# RGBMainBoard_-_SCH.net
KiCad netlist of a schematic drawn in Altium Designer
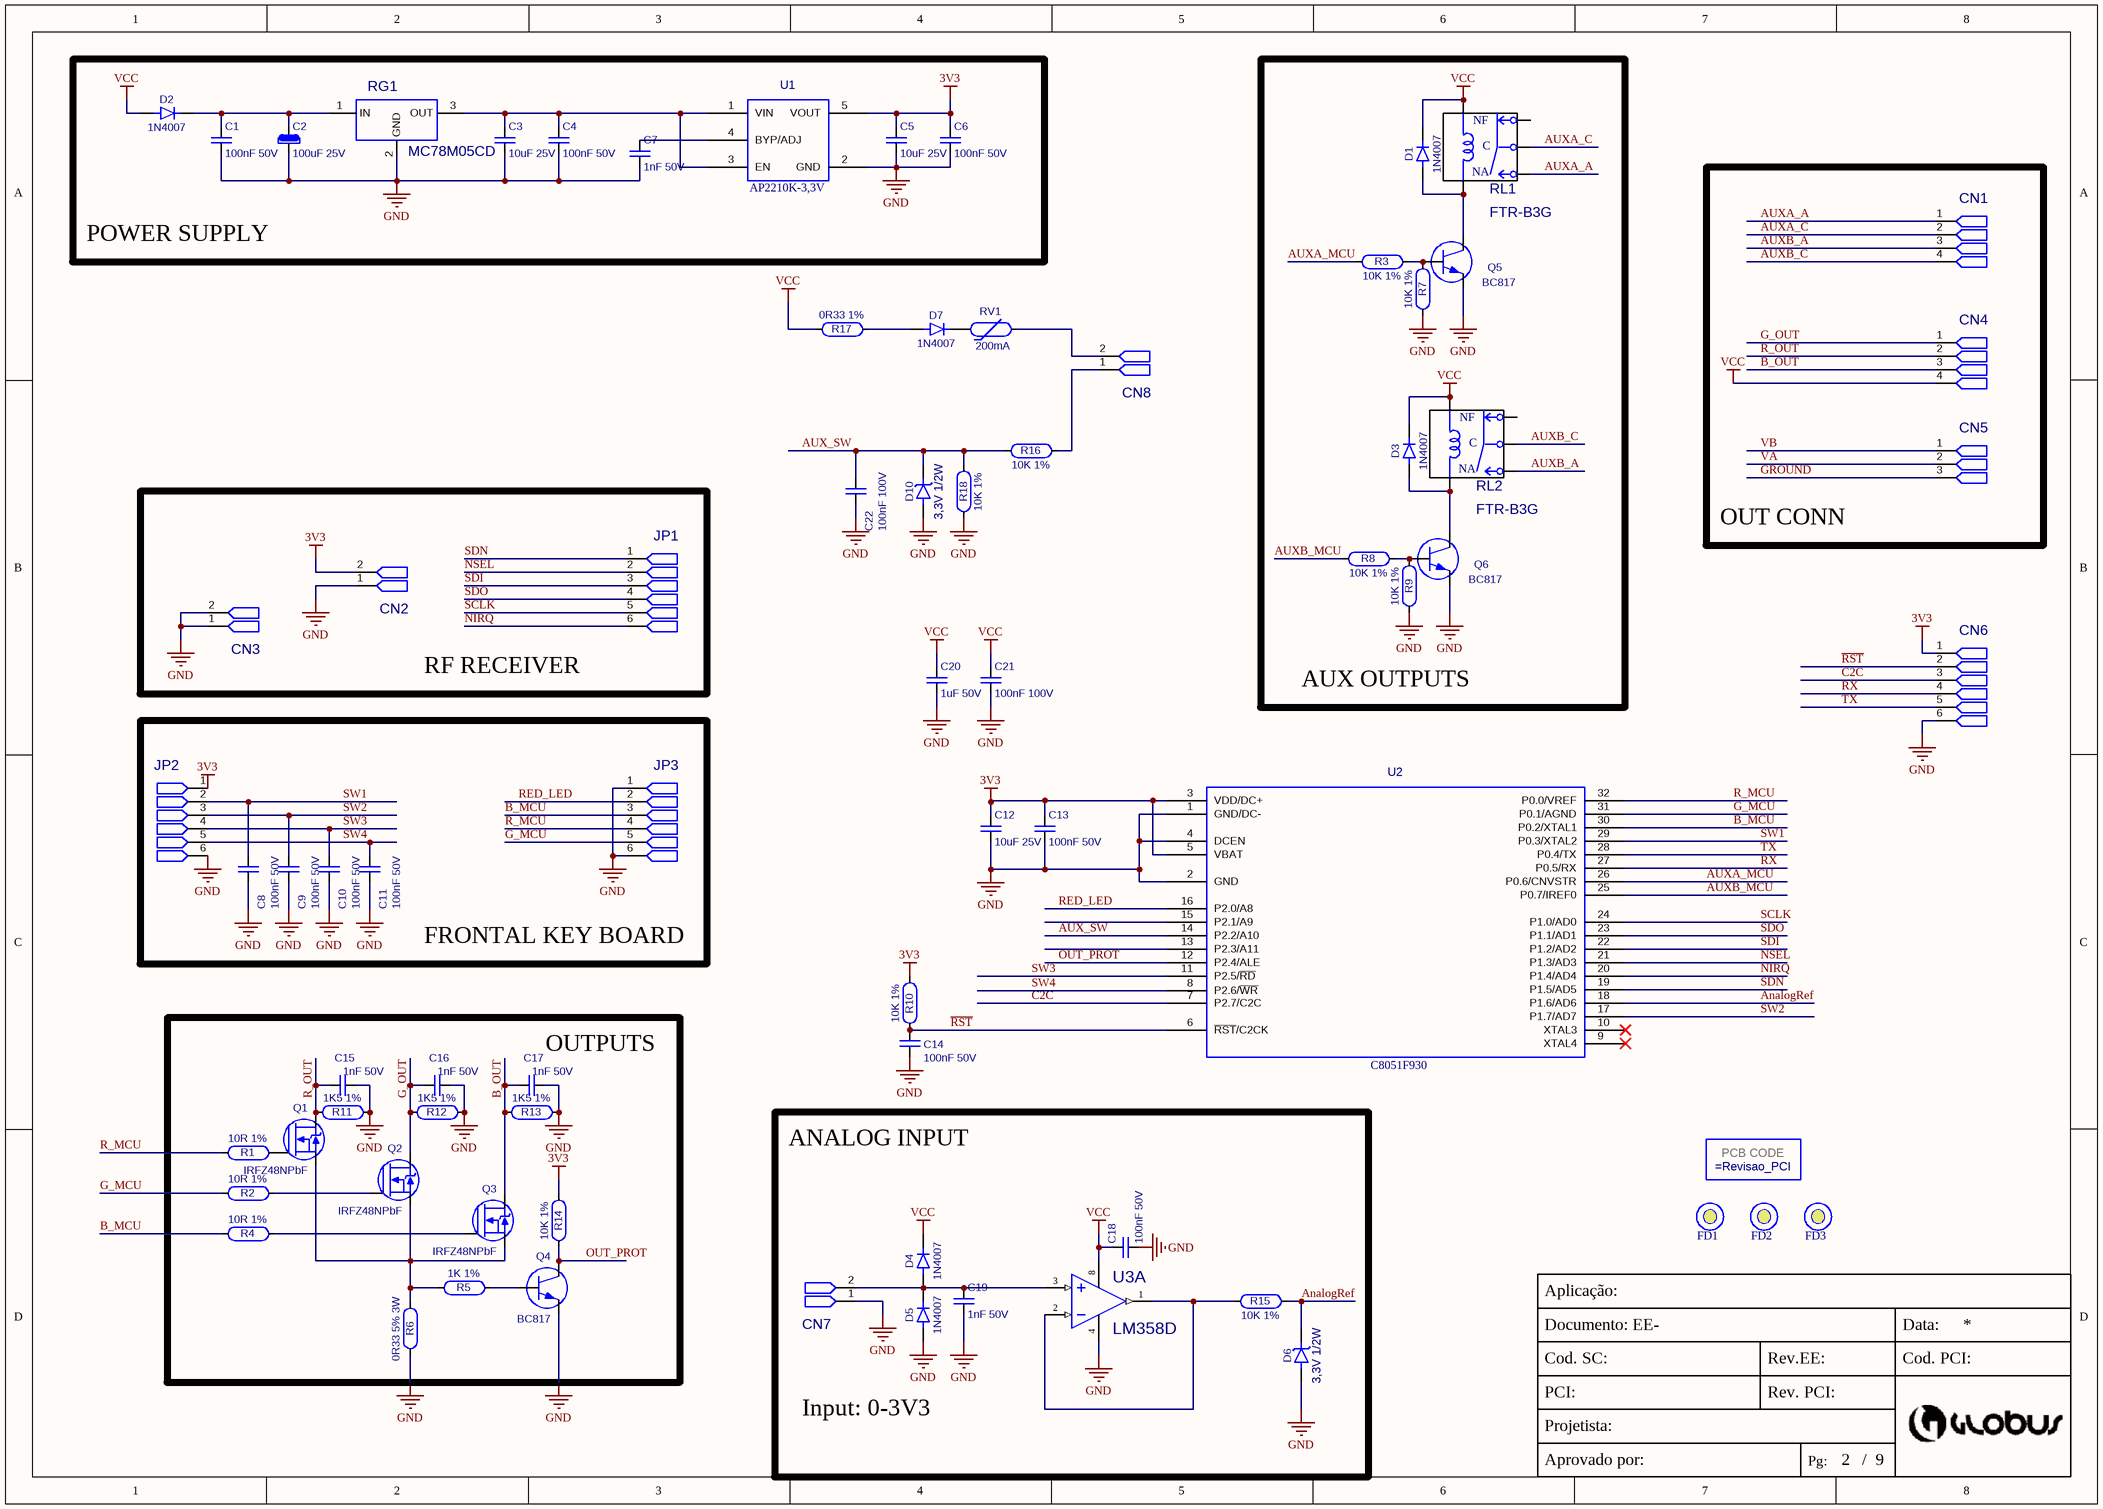
[diagram p0: RGBMainBoard - SCH.SchDoc]

(export (version "E")
  (design (tool "Eeschema 10.0.6"))
  (components
    (comp (ref "=Revisao_PCI")
      (value "*")
      (footprint "NULL_FOOTPRINT")
      (description "Preencher com o código da placa. Irá aparecer na serigrafia.")
      (libsource (lib "GLOBUS_ALTIUM") (part "CODIGO PCI"))
    )
    (comp (ref "C1")
      (value "100nF 50V")
      (footprint "C0805")
      (libsource (lib "GLOBUS_ALTIUM") (part "CC 100nF 50V 0805"))
    )
    (comp (ref "C2")
      (value "100uF 25V")
      (footprint "CAP100P_D6.3H11")
      (description "C.Elet.1000uF 25V 20% Radial")
      (libsource (lib "GLOBUS_ALTIUM") (part "CE 100uF 25V PTH"))
    )
    (comp (ref "C3")
      (value "10uF 25V")
      (footprint "C1206")
      (libsource (lib "GLOBUS_ALTIUM") (part "CC 10uF 25V 1206"))
    )
    (comp (ref "C4")
      (value "100nF 50V")
      (footprint "C0805")
      (libsource (lib "GLOBUS_ALTIUM") (part "CC 100nF 50V 0805"))
    )
    (comp (ref "C5")
      (value "10uF 25V")
      (footprint "C1206")
      (libsource (lib "GLOBUS_ALTIUM") (part "CC 10uF 25V 1206"))
    )
    (comp (ref "C6")
      (value "100nF 50V")
      (footprint "C0805")
      (libsource (lib "GLOBUS_ALTIUM") (part "CC 100nF 50V 0805"))
    )
    (comp (ref "C7")
      (value "1nF 50V")
      (footprint "C0805")
      (libsource (lib "GLOBUS_ALTIUM") (part "CC 1nF 50V 0805"))
    )
    (comp (ref "C8")
      (value "100nF 50V")
      (footprint "C0805")
      (libsource (lib "GLOBUS_ALTIUM") (part "CC 100nF 50V 0805"))
    )
    (comp (ref "C9")
      (value "100nF 50V")
      (footprint "C0805")
      (libsource (lib "GLOBUS_ALTIUM") (part "CC 100nF 50V 0805"))
    )
    (comp (ref "C10")
      (value "100nF 50V")
      (footprint "C0805")
      (libsource (lib "GLOBUS_ALTIUM") (part "CC 100nF 50V 0805"))
    )
    (comp (ref "C11")
      (value "100nF 50V")
      (footprint "C0805")
      (libsource (lib "GLOBUS_ALTIUM") (part "CC 100nF 50V 0805"))
    )
    (comp (ref "C12")
      (value "10uF 25V")
      (footprint "C1206")
      (libsource (lib "GLOBUS_ALTIUM") (part "CC 10uF 25V 1206"))
    )
    (comp (ref "C13")
      (value "100nF 50V")
      (footprint "C0805")
      (libsource (lib "GLOBUS_ALTIUM") (part "CC 100nF 50V 0805"))
    )
    (comp (ref "C14")
      (value "100nF 50V")
      (footprint "C0805")
      (libsource (lib "GLOBUS_ALTIUM") (part "CC 100nF 50V 0805"))
    )
    (comp (ref "C15")
      (value "1nF 50V")
      (footprint "C0805")
      (libsource (lib "GLOBUS_ALTIUM") (part "CC 1nF 50V 0805"))
    )
    (comp (ref "C16")
      (value "1nF 50V")
      (footprint "C0805")
      (libsource (lib "GLOBUS_ALTIUM") (part "CC 1nF 50V 0805"))
    )
    (comp (ref "C17")
      (value "1nF 50V")
      (footprint "C0805")
      (libsource (lib "GLOBUS_ALTIUM") (part "CC 1nF 50V 0805"))
    )
    (comp (ref "C18")
      (value "100nF 50V")
      (footprint "C0805")
      (libsource (lib "GLOBUS_ALTIUM") (part "CC 100nF 50V 0805"))
    )
    (comp (ref "C19")
      (value "1nF 50V")
      (footprint "C0805")
      (libsource (lib "GLOBUS_ALTIUM") (part "CC 1nF 50V 0805"))
    )
    (comp (ref "C20")
      (value "1uF 50V")
      (footprint "C0805")
      (libsource (lib "GLOBUS_ALTIUM") (part "CC 1uF 50V 0805"))
    )
    (comp (ref "C21")
      (value "100nF 100V")
      (footprint "C1206")
      (libsource (lib "GLOBUS_ALTIUM") (part "CC 100nF 100V 1206"))
    )
    (comp (ref "C22")
      (value "100nF 100V")
      (footprint "C1206")
      (libsource (lib "GLOBUS_ALTIUM") (part "CC 100nF 100V 1206"))
    )
    (comp (ref "CN1")
      (value "BORNE 4P 5.08")
      (footprint "BORNE 4P 5.08 PTH")
      (description "CON BORNE 4P 5.08 PTH")
      (fields (field (name "PART NUMBER") "BR8MN2-04"))
      (libsource (lib "GLOBUS_ALTIUM") (part "CON BORNE 4P 5.08 PTH"))
    )
    (comp (ref "CN2")
      (value "CON BARRA 1x2 180 MACHO PTH")
      (footprint "BARRA2PM180")
      (description "Barra de pinos simples 1x2 180g. 2,54mm")
      (fields (field (name "PART NUMBER") "{Part Number}"))
      (libsource (lib "GLOBUS_ALTIUM") (part "CON BARRA 1x2 180 MACHO PTH"))
    )
    (comp (ref "CN3")
      (value "CON BARRA 1x2 180 MACHO PTH")
      (footprint "BARRA2PM180")
      (description "Barra de pinos simples 1x2 180g. 2,54mm")
      (fields (field (name "PART NUMBER") "{Part Number}"))
      (libsource (lib "GLOBUS_ALTIUM") (part "CON BARRA 1x2 180 MACHO PTH"))
    )
    (comp (ref "CN4")
      (value "BORNE 4P 5.08")
      (footprint "BORNE 4P 5.08 PTH")
      (description "CON BORNE 4P 5.08 PTH")
      (fields (field (name "PART NUMBER") "BR8MN2-04"))
      (libsource (lib "GLOBUS_ALTIUM") (part "CON BORNE 4P 5.08 PTH"))
    )
    (comp (ref "CN5")
      (value "BORNE 3P 5.08")
      (footprint "BORNE 3P 5.08 PTH")
      (description "CON BORNE 3P 5.08 PTH")
      (fields (field (name "PART NUMBER") "BR8MN2-03"))
      (libsource (lib "GLOBUS_ALTIUM") (part "CON BORNE 3P 5.08 PTH"))
    )
    (comp (ref "CN6")
      (value "CON BARRA 1x6 180 MACHO PTH  17mm")
      (footprint "BARRA1x6PM180-17mm")
      (description "Barra de pinos simples 1x6 180g. 2,54mm")
      (fields (field (name "PART NUMBER") "{Part Number}"))
      (libsource (lib "GLOBUS_ALTIUM") (part "CON BARRA 1x6 180 MACHO PTH  17mm"))
    )
    (comp (ref "CN7")
      (value "CON BARRA 1x2 180 MACHO PTH")
      (footprint "BARRA2PM180")
      (description "Barra de pinos simples 1x2 180g. 2,54mm")
      (fields (field (name "PART NUMBER") "{Part Number}"))
      (libsource (lib "GLOBUS_ALTIUM") (part "CON BARRA 1x2 180 MACHO PTH"))
    )
    (comp (ref "CN8")
      (value "CON BARRA 1x2 180 MACHO PTH")
      (footprint "BARRA2PM180")
      (description "Barra de pinos simples 1x2 180g. 2,54mm")
      (fields (field (name "PART NUMBER") "{Part Number}"))
      (libsource (lib "GLOBUS_ALTIUM") (part "CON BARRA 1x2 180 MACHO PTH"))
    )
    (comp (ref "D1")
      (value "1N4007")
      (footprint "DO214AC-SMA")
      (description "Diodo 1N4007 (S1M-E3/5AT) DO214AC/SMA")
      (libsource (lib "GLOBUS_ALTIUM") (part "D 1N4007 SMD"))
    )
    (comp (ref "D2")
      (value "1N4007")
      (footprint "DO214AC-SMA")
      (description "Diodo 1N4007 (S1M-E3/5AT) DO214AC/SMA")
      (libsource (lib "GLOBUS_ALTIUM") (part "D 1N4007 SMD"))
    )
    (comp (ref "D3")
      (value "1N4007")
      (footprint "DO214AC-SMA")
      (description "Diodo 1N4007 (S1M-E3/5AT) DO214AC/SMA")
      (libsource (lib "GLOBUS_ALTIUM") (part "D 1N4007 SMD"))
    )
    (comp (ref "D4")
      (value "1N4007")
      (footprint "DO214AC-SMA")
      (description "Diodo 1N4007 (S1M-E3/5AT) DO214AC/SMA")
      (libsource (lib "GLOBUS_ALTIUM") (part "D 1N4007 SMD"))
    )
    (comp (ref "D5")
      (value "1N4007")
      (footprint "DO214AC-SMA")
      (description "Diodo 1N4007 (S1M-E3/5AT) DO214AC/SMA")
      (libsource (lib "GLOBUS_ALTIUM") (part "D 1N4007 SMD"))
    )
    (comp (ref "D6")
      (value "3,3V 1/2W")
      (footprint "SOD80-MINIMELF")
      (description "Zener 3,3V 1/2W MINIMELF")
      (libsource (lib "GLOBUS_ALTIUM") (part "DZ 3,3V 1/2W MINIMELF"))
    )
    (comp (ref "D7")
      (value "1N4007")
      (footprint "DO214AC-SMA")
      (description "Diodo 1N4007 (S1M-E3/5AT) DO214AC/SMA")
      (libsource (lib "GLOBUS_ALTIUM") (part "D 1N4007 SMD"))
    )
    (comp (ref "D10")
      (value "3,3V 1/2W")
      (footprint "SOD80-MINIMELF")
      (description "Zener 3,3V 1/2W MINIMELF")
      (libsource (lib "GLOBUS_ALTIUM") (part "DZ 3,3V 1/2W MINIMELF"))
    )
    (comp (ref "FD1")
      (value "Fiducial")
      (footprint "Fiducial")
      (libsource (lib "GLOBUS_ALTIUM") (part "Fiducial"))
    )
    (comp (ref "FD2")
      (value "Fiducial")
      (footprint "Fiducial")
      (libsource (lib "GLOBUS_ALTIUM") (part "Fiducial"))
    )
    (comp (ref "FD3")
      (value "Fiducial")
      (footprint "Fiducial")
      (libsource (lib "GLOBUS_ALTIUM") (part "Fiducial"))
    )
    (comp (ref "JP1")
      (value "CON BARRA 1x6 180 MACHO PTH")
      (footprint "BARRA6PM180")
      (description "Barra de pinos simples 1x6 180g. 2,54mm")
      (fields (field (name "PART NUMBER") "{Part Number}"))
      (libsource (lib "GLOBUS_ALTIUM") (part "CON BARRA 1x6 180 MACHO PTH"))
    )
    (comp (ref "JP2")
      (value "BARRA6PF180")
      (footprint "BARRA6PF180")
      (description "Barra de pinos simples 1x6 180g. 2,54mm")
      (fields (field (name "PART NUMBER") "{Part Number}"))
      (libsource (lib "GLOBUS_ALTIUM") (part "CON BARRA 1X6 180 FEMEA PTH"))
    )
    (comp (ref "JP3")
      (value "BARRA6PF180")
      (footprint "BARRA6PF180")
      (description "Barra de pinos simples 1x6 180g. 2,54mm")
      (fields (field (name "PART NUMBER") "{Part Number}"))
      (libsource (lib "GLOBUS_ALTIUM") (part "CON BARRA 1X6 180 FEMEA PTH"))
    )
    (comp (ref "Q1")
      (value "IRFZ48NPbF")
      (footprint "TO220AB")
      (description "TRAN CANAL N IRFZ48NPbF TO220")
      (libsource (lib "GLOBUS_ALTIUM") (part "TRAN CANAL N IRFZ48NPbF TO220"))
    )
    (comp (ref "Q2")
      (value "IRFZ48NPbF")
      (footprint "TO220AB")
      (description "TRAN CANAL N IRFZ48NPbF TO220")
      (libsource (lib "GLOBUS_ALTIUM") (part "TRAN CANAL N IRFZ48NPbF TO220"))
    )
    (comp (ref "Q3")
      (value "IRFZ48NPbF")
      (footprint "TO220AB")
      (description "TRAN CANAL N IRFZ48NPbF TO220")
      (libsource (lib "GLOBUS_ALTIUM") (part "TRAN CANAL N IRFZ48NPbF TO220"))
    )
    (comp (ref "Q4")
      (value "BC817")
      (footprint "SOT23")
      (description "SMT NPN 45V 0.5A SOT23 General Purpose Transistor")
      (libsource (lib "GLOBUS_ALTIUM") (part "TRAN NPN BC817 SOT-23-3"))
    )
    (comp (ref "Q5")
      (value "BC817")
      (footprint "SOT23")
      (description "SMT NPN 45V 0.5A SOT23 General Purpose Transistor")
      (libsource (lib "GLOBUS_ALTIUM") (part "TRAN NPN BC817 SOT-23-3"))
    )
    (comp (ref "Q6")
      (value "BC817")
      (footprint "SOT23")
      (description "SMT NPN 45V 0.5A SOT23 General Purpose Transistor")
      (libsource (lib "GLOBUS_ALTIUM") (part "TRAN NPN BC817 SOT-23-3"))
    )
    (comp (ref "R1")
      (value "10R 1%")
      (footprint "R0805")
      (description "RES 10R 1% 0805")
      (fields (field (name "PART NUMBER") "{Part Number}"))
      (libsource (lib "GLOBUS_ALTIUM") (part "RES 10R 1% 0805"))
    )
    (comp (ref "R2")
      (value "10R 1%")
      (footprint "R0805")
      (description "RES 10R 1% 0805")
      (fields (field (name "PART NUMBER") "{Part Number}"))
      (libsource (lib "GLOBUS_ALTIUM") (part "RES 10R 1% 0805"))
    )
    (comp (ref "R3")
      (value "10K 1%")
      (footprint "R0805")
      (description "RES 10K 1% 0805")
      (fields (field (name "PART NUMBER") "{Part Number}"))
      (libsource (lib "GLOBUS_ALTIUM") (part "RES 10K 1% 0805"))
    )
    (comp (ref "R4")
      (value "10R 1%")
      (footprint "R0805")
      (description "RES 10R 1% 0805")
      (fields (field (name "PART NUMBER") "{Part Number}"))
      (libsource (lib "GLOBUS_ALTIUM") (part "RES 10R 1% 0805"))
    )
    (comp (ref "R5")
      (value "1K 1%")
      (footprint "R0805")
      (description "RES 1K 1% 0805")
      (fields (field (name "PART NUMBER") "{Part Number}"))
      (libsource (lib "GLOBUS_ALTIUM") (part "RES 1K 1% 0805"))
    )
    (comp (ref "R6")
      (value "0R33 5% 3W")
      (footprint "RES2W_L16mm_D5.5")
      (description "RES 0R33 5% 3W PTH")
      (fields (field (name "PART NUMBER") "AC03000003307JAC00"))
      (libsource (lib "GLOBUS_ALTIUM") (part "RES 0R33 5% 3W PTH"))
    )
    (comp (ref "R7")
      (value "10K 1%")
      (footprint "R0805")
      (description "RES 10K 1% 0805")
      (fields (field (name "PART NUMBER") "{Part Number}"))
      (libsource (lib "GLOBUS_ALTIUM") (part "RES 10K 1% 0805"))
    )
    (comp (ref "R8")
      (value "10K 1%")
      (footprint "R0805")
      (description "RES 10K 1% 0805")
      (fields (field (name "PART NUMBER") "{Part Number}"))
      (libsource (lib "GLOBUS_ALTIUM") (part "RES 10K 1% 0805"))
    )
    (comp (ref "R9")
      (value "10K 1%")
      (footprint "R0805")
      (description "RES 10K 1% 0805")
      (fields (field (name "PART NUMBER") "{Part Number}"))
      (libsource (lib "GLOBUS_ALTIUM") (part "RES 10K 1% 0805"))
    )
    (comp (ref "R10")
      (value "10K 1%")
      (footprint "R0805")
      (description "RES 10K 1% 0805")
      (fields (field (name "PART NUMBER") "{Part Number}"))
      (libsource (lib "GLOBUS_ALTIUM") (part "RES 10K 1% 0805"))
    )
    (comp (ref "R11")
      (value "1K5 1%")
      (footprint "R0805")
      (description "RES 1K5 1% 0805")
      (fields (field (name "PART NUMBER") "{Part Number}"))
      (libsource (lib "GLOBUS_ALTIUM") (part "RES 1K5 1% 0805"))
    )
    (comp (ref "R12")
      (value "1K5 1%")
      (footprint "R0805")
      (description "RES 1K5 1% 0805")
      (fields (field (name "PART NUMBER") "{Part Number}"))
      (libsource (lib "GLOBUS_ALTIUM") (part "RES 1K5 1% 0805"))
    )
    (comp (ref "R13")
      (value "1K5 1%")
      (footprint "R0805")
      (description "RES 1K5 1% 0805")
      (fields (field (name "PART NUMBER") "{Part Number}"))
      (libsource (lib "GLOBUS_ALTIUM") (part "RES 1K5 1% 0805"))
    )
    (comp (ref "R14")
      (value "10K 1%")
      (footprint "R0805")
      (description "RES 10K 1% 0805")
      (fields (field (name "PART NUMBER") "{Part Number}"))
      (libsource (lib "GLOBUS_ALTIUM") (part "RES 10K 1% 0805"))
    )
    (comp (ref "R15")
      (value "10K 1%")
      (footprint "R0805")
      (description "RES 10K 1% 0805")
      (fields (field (name "PART NUMBER") "{Part Number}"))
      (libsource (lib "GLOBUS_ALTIUM") (part "RES 10K 1% 0805"))
    )
    (comp (ref "R16")
      (value "10K 1%")
      (footprint "R0805")
      (description "RES 10K 1% 0805")
      (fields (field (name "PART NUMBER") "{Part Number}"))
      (libsource (lib "GLOBUS_ALTIUM") (part "RES 10K 1% 0805"))
    )
    (comp (ref "R17")
      (value "0R33 1%")
      (footprint "R1206")
      (description "RES 0R33 1% 1206")
      (fields (field (name "PART NUMBER") "{Part Number}"))
      (libsource (lib "GLOBUS_ALTIUM") (part "RES 0R33 1% 1206"))
    )
    (comp (ref "R18")
      (value "10K 1%")
      (footprint "R0805")
      (description "RES 10K 1% 0805")
      (fields (field (name "PART NUMBER") "{Part Number}"))
      (libsource (lib "GLOBUS_ALTIUM") (part "RES 10K 1% 0805"))
    )
    (comp (ref "RG1")
      (value "MC78M05CD")
      (footprint "DPAK")
      (description "5V 1A DPAK-3 3 Terminal  Positive Voltage Regulator")
      (libsource (lib "GLOBUS_ALTIUM") (part "CI REG LIN 5V MC78M05CD DPAK"))
    )
    (comp (ref "RL1")
      (value "FTR-B3G")
      (footprint "RELE_HF3FF-SERIE")
      (description "RELE 12V HF3FF/012-1ZST")
      (fields (field (name "PART NUMBER") "HF3FF/012-1ZST"))
      (libsource (lib "GLOBUS_ALTIUM") (part "RELE 12V HF3FF/012-1ZST"))
    )
    (comp (ref "RL2")
      (value "FTR-B3G")
      (footprint "RELE_HF3FF-SERIE")
      (description "RELE 12V HF3FF/012-1ZST")
      (fields (field (name "PART NUMBER") "HF3FF/012-1ZST"))
      (libsource (lib "GLOBUS_ALTIUM") (part "RELE 12V HF3FF/012-1ZST"))
    )
    (comp (ref "RV1")
      (value "200mA")
      (footprint "PTC5.1_7.4X3.1mm")
      (description "R POLYSWITCH 60R020XU PTH")
      (fields (field (name "PART NUMBER") "60R020XU"))
      (libsource (lib "GLOBUS_ALTIUM") (part "R POLYSWITCH 60R020XU"))
    )
    (comp (ref "U1")
      (value "AP2210K-3,3V")
      (footprint "SOT23_5")
      (description "AP2210 300mA RF ULDO REGLATOR SOT23-5")
      (libsource (lib "GLOBUS_ALTIUM") (part "CI REG LDO 3,3V AP2210K"))
    )
    (comp (ref "U2")
      (value "C8051F930")
      (footprint "LQFP32 7X7")
      (description "C8051F930 LQFP32")
      (fields (field (name "PART NUMBER") "C8051F930-G-GQ"))
      (libsource (lib "GLOBUS_ALTIUM") (part "CI PROC C8051F930 LQFP32"))
    )
    (comp (ref "U3")
      (value "LM358D")
      (footprint "SO8")
      (description "Low Power Dual Operational Amplifier SMT SO8")
      (libsource (lib "GLOBUS_ALTIUM") (part "CI LM358D SO8"))
    )
  )
  (nets
    (net (code "1") (name "/AUXA_A") (class "Default")
      (node (ref "CN1") (pin "1") (pinfunction "1_1") (pintype "passive"))
      (node (ref "RL1") (pin "4") (pinfunction "NA_4") (pintype "passive"))
    )
    (net (code "2") (name "/AUXA_C") (class "Default")
      (node (ref "CN1") (pin "2") (pinfunction "2_2") (pintype "passive"))
      (node (ref "RL1") (pin "3") (pinfunction "C_3") (pintype "passive"))
    )
    (net (code "3") (name "/AUXA_MCU") (class "Default")
      (node (ref "R3") (pin "2") (pinfunction "2_2") (pintype "passive"))
      (node (ref "U2") (pin "26") (pinfunction "P0.6/CNVSTR_26") (pintype "passive"))
    )
    (net (code "4") (name "/AUXB_A") (class "Default")
      (node (ref "CN1") (pin "3") (pinfunction "3_3") (pintype "passive"))
      (node (ref "RL2") (pin "4") (pinfunction "NA_4") (pintype "passive"))
    )
    (net (code "5") (name "/AUXB_C") (class "Default")
      (node (ref "CN1") (pin "4") (pinfunction "4_4") (pintype "passive"))
      (node (ref "RL2") (pin "3") (pinfunction "C_3") (pintype "passive"))
    )
    (net (code "6") (name "/AUXB_MCU") (class "Default")
      (node (ref "R8") (pin "2") (pinfunction "2_2") (pintype "passive"))
      (node (ref "U2") (pin "25") (pinfunction "P0.7/IREF0_25") (pintype "passive"))
    )
    (net (code "7") (name "/AUX_SW") (class "Default")
      (node (ref "C22") (pin "1") (pinfunction "1_1") (pintype "passive"))
      (node (ref "D10") (pin "2") (pinfunction "cathode_2") (pintype "passive"))
      (node (ref "R16") (pin "2") (pinfunction "2_2") (pintype "passive"))
      (node (ref "R18") (pin "1") (pinfunction "1_1") (pintype "passive"))
      (node (ref "U2") (pin "14") (pinfunction "P2.2/A10_14") (pintype "passive"))
    )
    (net (code "8") (name "/AnalogRef") (class "Default")
      (node (ref "D6") (pin "2") (pinfunction "cathode_2") (pintype "passive"))
      (node (ref "R15") (pin "1") (pinfunction "1_1") (pintype "passive"))
      (node (ref "U2") (pin "18") (pinfunction "P1.6/AD6_18") (pintype "passive"))
    )
    (net (code "9") (name "/B_MCU") (class "Default")
      (node (ref "JP3") (pin "3") (pinfunction "3_3") (pintype "passive"))
      (node (ref "R4") (pin "1") (pinfunction "1_1") (pintype "passive"))
      (node (ref "U2") (pin "30") (pinfunction "P0.2/XTAL1_30") (pintype "passive"))
    )
    (net (code "10") (name "/B_OUT") (class "Default")
      (node (ref "C17") (pin "1") (pinfunction "1_1") (pintype "passive"))
      (node (ref "CN4") (pin "3") (pinfunction "3_3") (pintype "passive"))
      (node (ref "Q3") (pin "2") (pinfunction "D_2") (pintype "passive"))
      (node (ref "R13") (pin "1") (pinfunction "1_1") (pintype "passive"))
    )
    (net (code "11") (name "/C2C") (class "Default")
      (node (ref "CN6") (pin "3") (pinfunction "3_3") (pintype "passive"))
      (node (ref "U2") (pin "7") (pinfunction "P2.7/C2C_7") (pintype "passive"))
    )
    (net (code "12") (name "/GROUND") (class "Default")
      (node (ref "CN5") (pin "3") (pinfunction "3_3") (pintype "passive"))
    )
    (net (code "13") (name "/G_MCU") (class "Default")
      (node (ref "JP3") (pin "5") (pinfunction "5_5") (pintype "passive"))
      (node (ref "R2") (pin "1") (pinfunction "1_1") (pintype "passive"))
      (node (ref "U2") (pin "31") (pinfunction "P0.1/AGND_31") (pintype "passive"))
    )
    (net (code "14") (name "/G_OUT") (class "Default")
      (node (ref "C16") (pin "1") (pinfunction "1_1") (pintype "passive"))
      (node (ref "CN4") (pin "1") (pinfunction "1_1") (pintype "passive"))
      (node (ref "Q2") (pin "2") (pinfunction "D_2") (pintype "passive"))
      (node (ref "R12") (pin "1") (pinfunction "1_1") (pintype "passive"))
    )
    (net (code "15") (name "/NIRQ") (class "Default")
      (node (ref "JP1") (pin "6") (pinfunction "6_6") (pintype "passive"))
      (node (ref "U2") (pin "20") (pinfunction "P1.4/AD4_20") (pintype "passive"))
    )
    (net (code "16") (name "/NSEL") (class "Default")
      (node (ref "JP1") (pin "2") (pinfunction "2_2") (pintype "passive"))
      (node (ref "U2") (pin "21") (pinfunction "P1.3/AD3_21") (pintype "passive"))
    )
    (net (code "17") (name "/OUT_PROT") (class "Default")
      (node (ref "Q4") (pin "2") (pinfunction "C_2") (pintype "passive"))
      (node (ref "R14") (pin "1") (pinfunction "1_1") (pintype "passive"))
      (node (ref "U2") (pin "12") (pinfunction "P2.4/ALE_12") (pintype "passive"))
    )
    (net (code "18") (name "/RED_LED") (class "Default")
      (node (ref "JP3") (pin "2") (pinfunction "2_2") (pintype "passive"))
      (node (ref "U2") (pin "16") (pinfunction "P2.0/A8_16") (pintype "passive"))
    )
    (net (code "19") (name "/RX") (class "Default")
      (node (ref "CN6") (pin "4") (pinfunction "4_4") (pintype "passive"))
      (node (ref "U2") (pin "27") (pinfunction "P0.5/RX_27") (pintype "passive"))
    )
    (net (code "20") (name "/R_MCU") (class "Default")
      (node (ref "JP3") (pin "4") (pinfunction "4_4") (pintype "passive"))
      (node (ref "R1") (pin "1") (pinfunction "1_1") (pintype "passive"))
      (node (ref "U2") (pin "32") (pinfunction "P0.0/VREF_32") (pintype "passive"))
    )
    (net (code "21") (name "/R_OUT") (class "Default")
      (node (ref "C15") (pin "1") (pinfunction "1_1") (pintype "passive"))
      (node (ref "CN4") (pin "2") (pinfunction "2_2") (pintype "passive"))
      (node (ref "Q1") (pin "2") (pinfunction "D_2") (pintype "passive"))
      (node (ref "R11") (pin "1") (pinfunction "1_1") (pintype "passive"))
    )
    (net (code "22") (name "/SCLK") (class "Default")
      (node (ref "JP1") (pin "5") (pinfunction "5_5") (pintype "passive"))
      (node (ref "U2") (pin "24") (pinfunction "P1.0/AD0_24") (pintype "passive"))
    )
    (net (code "23") (name "/SDI") (class "Default")
      (node (ref "JP1") (pin "3") (pinfunction "3_3") (pintype "passive"))
      (node (ref "U2") (pin "22") (pinfunction "P1.2/AD2_22") (pintype "passive"))
    )
    (net (code "24") (name "/SDN") (class "Default")
      (node (ref "JP1") (pin "1") (pinfunction "1_1") (pintype "passive"))
      (node (ref "U2") (pin "19") (pinfunction "P1.5/AD5_19") (pintype "passive"))
    )
    (net (code "25") (name "/SDO") (class "Default")
      (node (ref "JP1") (pin "4") (pinfunction "4_4") (pintype "passive"))
      (node (ref "U2") (pin "23") (pinfunction "P1.1/AD1_23") (pintype "passive"))
    )
    (net (code "26") (name "/SW1") (class "Default")
      (node (ref "C8") (pin "1") (pinfunction "1_1") (pintype "passive"))
      (node (ref "JP2") (pin "2") (pinfunction "2_2") (pintype "passive"))
      (node (ref "U2") (pin "29") (pinfunction "P0.3/XTAL2_29") (pintype "passive"))
    )
    (net (code "27") (name "/SW2") (class "Default")
      (node (ref "C9") (pin "1") (pinfunction "1_1") (pintype "passive"))
      (node (ref "JP2") (pin "3") (pinfunction "3_3") (pintype "passive"))
      (node (ref "U2") (pin "17") (pinfunction "P1.7/AD7_17") (pintype "passive"))
    )
    (net (code "28") (name "/SW3") (class "Default")
      (node (ref "C10") (pin "1") (pinfunction "1_1") (pintype "passive"))
      (node (ref "JP2") (pin "4") (pinfunction "4_4") (pintype "passive"))
      (node (ref "U2") (pin "11") (pinfunction "P2.5/~{RD}_11") (pintype "passive"))
    )
    (net (code "29") (name "/SW4") (class "Default")
      (node (ref "C11") (pin "1") (pinfunction "1_1") (pintype "passive"))
      (node (ref "JP2") (pin "5") (pinfunction "5_5") (pintype "passive"))
      (node (ref "U2") (pin "8") (pinfunction "P2.6/~{WR}_8") (pintype "passive"))
    )
    (net (code "30") (name "/TX") (class "Default")
      (node (ref "CN6") (pin "5") (pinfunction "5_5") (pintype "passive"))
      (node (ref "U2") (pin "28") (pinfunction "P0.4/TX_28") (pintype "passive"))
    )
    (net (code "31") (name "/VA") (class "Default")
      (node (ref "CN5") (pin "2") (pinfunction "2_2") (pintype "passive"))
    )
    (net (code "32") (name "/VB") (class "Default")
      (node (ref "CN5") (pin "1") (pinfunction "1_1") (pintype "passive"))
    )
    (net (code "33") (name "/~{RST}") (class "Default")
      (node (ref "C14") (pin "1") (pinfunction "1_1") (pintype "passive"))
      (node (ref "CN6") (pin "2") (pinfunction "2_2") (pintype "passive"))
      (node (ref "R10") (pin "1") (pinfunction "1_1") (pintype "passive"))
      (node (ref "U2") (pin "6") (pinfunction "~{RST}/C2CK_6") (pintype "passive"))
    )
    (net (code "34") (name "3V3") (class "Default")
      (node (ref "C12") (pin "1") (pinfunction "1_1") (pintype "passive"))
      (node (ref "C13") (pin "1") (pinfunction "1_1") (pintype "passive"))
      (node (ref "C5") (pin "1") (pinfunction "1_1") (pintype "passive"))
      (node (ref "C6") (pin "1") (pinfunction "1_1") (pintype "passive"))
      (node (ref "CN2") (pin "2") (pinfunction "2_2") (pintype "passive"))
      (node (ref "CN6") (pin "1") (pinfunction "1_1") (pintype "passive"))
      (node (ref "JP2") (pin "1") (pinfunction "1_1") (pintype "passive"))
      (node (ref "R10") (pin "2") (pinfunction "2_2") (pintype "passive"))
      (node (ref "R14") (pin "2") (pinfunction "2_2") (pintype "passive"))
      (node (ref "U1") (pin "5") (pinfunction "VOUT_5") (pintype "passive"))
      (node (ref "U2") (pin "3") (pinfunction "VDD/DC+_3") (pintype "passive"))
      (node (ref "U2") (pin "5") (pinfunction "VBAT_5") (pintype "passive"))
    )
    (net (code "35") (name "GND") (class "Default")
      (node (ref "C1") (pin "2") (pinfunction "2_2") (pintype "passive"))
      (node (ref "C10") (pin "2") (pinfunction "2_2") (pintype "passive"))
      (node (ref "C11") (pin "2") (pinfunction "2_2") (pintype "passive"))
      (node (ref "C12") (pin "2") (pinfunction "2_2") (pintype "passive"))
      (node (ref "C13") (pin "2") (pinfunction "2_2") (pintype "passive"))
      (node (ref "C14") (pin "2") (pinfunction "2_2") (pintype "passive"))
      (node (ref "C15") (pin "2") (pinfunction "2_2") (pintype "passive"))
      (node (ref "C16") (pin "2") (pinfunction "2_2") (pintype "passive"))
      (node (ref "C17") (pin "2") (pinfunction "2_2") (pintype "passive"))
      (node (ref "C18") (pin "2") (pinfunction "2_2") (pintype "passive"))
      (node (ref "C19") (pin "2") (pinfunction "2_2") (pintype "passive"))
      (node (ref "C2") (pin "1") (pinfunction "negative_1") (pintype "passive"))
      (node (ref "C20") (pin "2") (pinfunction "2_2") (pintype "passive"))
      (node (ref "C21") (pin "2") (pinfunction "2_2") (pintype "passive"))
      (node (ref "C22") (pin "2") (pinfunction "2_2") (pintype "passive"))
      (node (ref "C3") (pin "2") (pinfunction "2_2") (pintype "passive"))
      (node (ref "C4") (pin "2") (pinfunction "2_2") (pintype "passive"))
      (node (ref "C5") (pin "2") (pinfunction "2_2") (pintype "passive"))
      (node (ref "C6") (pin "2") (pinfunction "2_2") (pintype "passive"))
      (node (ref "C7") (pin "2") (pinfunction "2_2") (pintype "passive"))
      (node (ref "C8") (pin "2") (pinfunction "2_2") (pintype "passive"))
      (node (ref "C9") (pin "2") (pinfunction "2_2") (pintype "passive"))
      (node (ref "CN2") (pin "1") (pinfunction "1_1") (pintype "passive"))
      (node (ref "CN3") (pin "1") (pinfunction "1_1") (pintype "passive"))
      (node (ref "CN3") (pin "2") (pinfunction "2_2") (pintype "passive"))
      (node (ref "CN6") (pin "6") (pinfunction "6_6") (pintype "passive"))
      (node (ref "CN7") (pin "1") (pinfunction "1_1") (pintype "passive"))
      (node (ref "D10") (pin "1") (pinfunction "anode_1") (pintype "passive"))
      (node (ref "D5") (pin "1") (pinfunction "anode_1") (pintype "passive"))
      (node (ref "D6") (pin "1") (pinfunction "anode_1") (pintype "passive"))
      (node (ref "JP2") (pin "6") (pinfunction "6_6") (pintype "passive"))
      (node (ref "JP3") (pin "1") (pinfunction "1_1") (pintype "passive"))
      (node (ref "JP3") (pin "6") (pinfunction "6_6") (pintype "passive"))
      (node (ref "Q4") (pin "3") (pinfunction "E_3") (pintype "passive"))
      (node (ref "Q5") (pin "3") (pinfunction "E_3") (pintype "passive"))
      (node (ref "Q6") (pin "3") (pinfunction "E_3") (pintype "passive"))
      (node (ref "R11") (pin "2") (pinfunction "2_2") (pintype "passive"))
      (node (ref "R12") (pin "2") (pinfunction "2_2") (pintype "passive"))
      (node (ref "R13") (pin "2") (pinfunction "2_2") (pintype "passive"))
      (node (ref "R18") (pin "2") (pinfunction "2_2") (pintype "passive"))
      (node (ref "R6") (pin "1") (pinfunction "1_1") (pintype "passive"))
      (node (ref "R7") (pin "1") (pinfunction "1_1") (pintype "passive"))
      (node (ref "R9") (pin "1") (pinfunction "1_1") (pintype "passive"))
      (node (ref "RG1") (pin "2") (pinfunction "GND_2") (pintype "passive"))
      (node (ref "U1") (pin "2") (pinfunction "GND_2") (pintype "passive"))
      (node (ref "U2") (pin "1") (pinfunction "GND/DC-_1") (pintype "passive"))
      (node (ref "U2") (pin "2") (pinfunction "GND_2") (pintype "passive"))
      (node (ref "U2") (pin "4") (pinfunction "DCEN_4") (pintype "passive"))
      (node (ref "U3") (pin "4") (pinfunction "GND_4") (pintype "power_in"))
    )
    (net (code "36") (name "Net-(C2-positive)") (class "Default")
      (node (ref "C1") (pin "1") (pinfunction "1_1") (pintype "passive"))
      (node (ref "C2") (pin "2") (pinfunction "positive_2") (pintype "passive"))
      (node (ref "D2") (pin "2") (pinfunction "cathode_2") (pintype "passive"))
      (node (ref "RG1") (pin "1") (pinfunction "IN_1") (pintype "passive"))
    )
    (net (code "37") (name "Net-(CN8-Pad1)") (class "Default")
      (node (ref "CN8") (pin "1") (pinfunction "1_1") (pintype "passive"))
      (node (ref "R16") (pin "1") (pinfunction "1_1") (pintype "passive"))
    )
    (net (code "38") (name "Net-(CN8-Pad2)") (class "Default")
      (node (ref "CN8") (pin "2") (pinfunction "2_2") (pintype "passive"))
      (node (ref "RV1") (pin "2") (pinfunction "2_2") (pintype "passive"))
    )
    (net (code "39") (name "Net-(D1-anode)") (class "Default")
      (node (ref "D1") (pin "1") (pinfunction "anode_1") (pintype "passive"))
      (node (ref "Q5") (pin "2") (pinfunction "C_2") (pintype "passive"))
      (node (ref "RL1") (pin "2") (pinfunction "B2_2") (pintype "passive"))
    )
    (net (code "40") (name "Net-(D3-anode)") (class "Default")
      (node (ref "D3") (pin "1") (pinfunction "anode_1") (pintype "passive"))
      (node (ref "Q6") (pin "2") (pinfunction "C_2") (pintype "passive"))
      (node (ref "RL2") (pin "2") (pinfunction "B2_2") (pintype "passive"))
    )
    (net (code "41") (name "Net-(D4-anode)") (class "Default")
      (node (ref "C19") (pin "1") (pinfunction "1_1") (pintype "passive"))
      (node (ref "CN7") (pin "2") (pinfunction "2_2") (pintype "passive"))
      (node (ref "D4") (pin "1") (pinfunction "anode_1") (pintype "passive"))
      (node (ref "D5") (pin "2") (pinfunction "cathode_2") (pintype "passive"))
      (node (ref "U3") (pin "3") (pinfunction "IN+_3") (pintype "input"))
    )
    (net (code "42") (name "Net-(D7-anode)") (class "Default")
      (node (ref "D7") (pin "1") (pinfunction "anode_1") (pintype "passive"))
      (node (ref "R17") (pin "2") (pinfunction "2_2") (pintype "passive"))
    )
    (net (code "43") (name "Net-(D7-cathode)") (class "Default")
      (node (ref "D7") (pin "2") (pinfunction "cathode_2") (pintype "passive"))
      (node (ref "RV1") (pin "1") (pinfunction "1_1") (pintype "passive"))
    )
    (net (code "44") (name "Net-(Q1-G)") (class "Default")
      (node (ref "Q1") (pin "1") (pinfunction "G_1") (pintype "passive"))
      (node (ref "R1") (pin "2") (pinfunction "2_2") (pintype "passive"))
    )
    (net (code "45") (name "Net-(Q1-S)") (class "Default")
      (node (ref "Q1") (pin "3") (pinfunction "S_3") (pintype "passive"))
      (node (ref "Q2") (pin "3") (pinfunction "S_3") (pintype "passive"))
      (node (ref "Q3") (pin "3") (pinfunction "S_3") (pintype "passive"))
      (node (ref "R5") (pin "1") (pinfunction "1_1") (pintype "passive"))
      (node (ref "R6") (pin "2") (pinfunction "2_2") (pintype "passive"))
    )
    (net (code "46") (name "Net-(Q2-G)") (class "Default")
      (node (ref "Q2") (pin "1") (pinfunction "G_1") (pintype "passive"))
      (node (ref "R2") (pin "2") (pinfunction "2_2") (pintype "passive"))
    )
    (net (code "47") (name "Net-(Q3-G)") (class "Default")
      (node (ref "Q3") (pin "1") (pinfunction "G_1") (pintype "passive"))
      (node (ref "R4") (pin "2") (pinfunction "2_2") (pintype "passive"))
    )
    (net (code "48") (name "Net-(Q4-B)") (class "Default")
      (node (ref "Q4") (pin "1") (pinfunction "B_1") (pintype "passive"))
      (node (ref "R5") (pin "2") (pinfunction "2_2") (pintype "passive"))
    )
    (net (code "49") (name "Net-(Q5-B)") (class "Default")
      (node (ref "Q5") (pin "1") (pinfunction "B_1") (pintype "passive"))
      (node (ref "R3") (pin "1") (pinfunction "1_1") (pintype "passive"))
      (node (ref "R7") (pin "2") (pinfunction "2_2") (pintype "passive"))
    )
    (net (code "50") (name "Net-(Q6-B)") (class "Default")
      (node (ref "Q6") (pin "1") (pinfunction "B_1") (pintype "passive"))
      (node (ref "R8") (pin "1") (pinfunction "1_1") (pintype "passive"))
      (node (ref "R9") (pin "2") (pinfunction "2_2") (pintype "passive"))
    )
    (net (code "51") (name "Net-(RG1-OUT)") (class "Default")
      (node (ref "C3") (pin "1") (pinfunction "1_1") (pintype "passive"))
      (node (ref "C4") (pin "1") (pinfunction "1_1") (pintype "passive"))
      (node (ref "RG1") (pin "3") (pinfunction "OUT_3") (pintype "passive"))
      (node (ref "U1") (pin "1") (pinfunction "VIN_1") (pintype "passive"))
      (node (ref "U1") (pin "3") (pinfunction "EN_3") (pintype "passive"))
    )
    (net (code "52") (name "Net-(U1-BYP{slash}ADJ)") (class "Default")
      (node (ref "C7") (pin "1") (pinfunction "1_1") (pintype "passive"))
      (node (ref "U1") (pin "4") (pinfunction "BYP/ADJ_4") (pintype "passive"))
    )
    (net (code "53") (name "Net-(U3A-IN-)") (class "Default")
      (node (ref "R15") (pin "2") (pinfunction "2_2") (pintype "passive"))
      (node (ref "U3") (pin "1") (pinfunction "OUT_1") (pintype "output"))
      (node (ref "U3") (pin "2") (pinfunction "IN-_2") (pintype "input"))
    )
    (net (code "54") (name "VCC") (class "Default")
      (node (ref "C18") (pin "1") (pinfunction "1_1") (pintype "passive"))
      (node (ref "C20") (pin "1") (pinfunction "1_1") (pintype "passive"))
      (node (ref "C21") (pin "1") (pinfunction "1_1") (pintype "passive"))
      (node (ref "CN4") (pin "4") (pinfunction "4_4") (pintype "passive"))
      (node (ref "D1") (pin "2") (pinfunction "cathode_2") (pintype "passive"))
      (node (ref "D2") (pin "1") (pinfunction "anode_1") (pintype "passive"))
      (node (ref "D3") (pin "2") (pinfunction "cathode_2") (pintype "passive"))
      (node (ref "D4") (pin "2") (pinfunction "cathode_2") (pintype "passive"))
      (node (ref "R17") (pin "1") (pinfunction "1_1") (pintype "passive"))
      (node (ref "RL1") (pin "1") (pinfunction "B1_1") (pintype "passive"))
      (node (ref "RL2") (pin "1") (pinfunction "B1_1") (pintype "passive"))
      (node (ref "U3") (pin "8") (pinfunction "V+_8") (pintype "power_in"))
    )
    (net (code "55") (name "unconnected-(RL1-NF-Pad5)") (class "Default")
      (node (ref "RL1") (pin "5") (pinfunction "NF_5") (pintype "passive"))
    )
    (net (code "56") (name "unconnected-(RL2-NF-Pad5)") (class "Default")
      (node (ref "RL2") (pin "5") (pinfunction "NF_5") (pintype "passive"))
    )
    (net (code "57") (name "unconnected-(U2-P2.1{slash}A9-Pad15)") (class "Default")
      (node (ref "U2") (pin "15") (pinfunction "P2.1/A9_15") (pintype "passive"))
    )
    (net (code "58") (name "unconnected-(U2-P2.3{slash}A11-Pad13)") (class "Default")
      (node (ref "U2") (pin "13") (pinfunction "P2.3/A11_13") (pintype "passive"))
    )
    (net (code "59") (name "unconnected-(U2-XTAL3-Pad10)") (class "Default")
      (node (ref "U2") (pin "10") (pinfunction "XTAL3_10") (pintype "passive+no_connect"))
    )
    (net (code "60") (name "unconnected-(U2-XTAL4-Pad9)") (class "Default")
      (node (ref "U2") (pin "9") (pinfunction "XTAL4_9") (pintype "passive+no_connect"))
    )
  )
)
